# kossr2.net
KiCad netlist of a schematic drawn in EAGLE
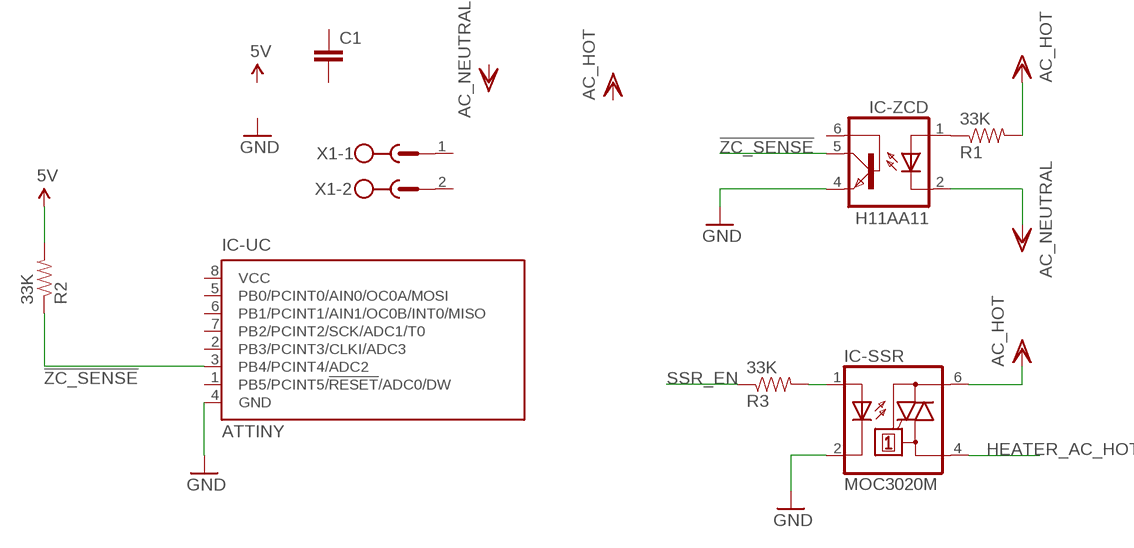
[diagram p0: schematic, sheet 1]

(export (version "E")
  (design (tool "Eeschema 10.0.6"))
  (components
    (comp (ref "C1")
      (value "CAPPTH")
      (footprint "eagle-import:CAP-PTH-SMALL")
      (libsource (lib "eagle-import") (part "CAPPTH"))
    )
    (comp (ref "IC-SSR")
      (value "MOC3020M")
      (footprint "eagle-import:DIL06")
      (fields (field (name "MF") "FAIRCHILD SEMICONDUCTOR") (field (name "MPN") "MOC3020-M"))
      (libsource (lib "eagle-import") (part "MOC30M20"))
    )
    (comp (ref "IC-UC")
      (value "ATTINY")
      (footprint "eagle-import:DIL08")
      (fields (field (name "MPN") "ATTINY13V-10PU"))
      (libsource (lib "eagle-import") (part "TINY13PUV-10"))
    )
    (comp (ref "IC-ZCD")
      (value "H11AA11")
      (footprint "eagle-import:DIL06")
      (fields (field (name "MPN") "H11A1-M"))
      (libsource (lib "eagle-import") (part "H11AA11"))
    )
    (comp (ref "R1")
      (value "33K")
      (footprint "eagle-import:AXIAL-0.4")
      (libsource (lib "eagle-import") (part "RESISTORPTH-1/4W"))
    )
    (comp (ref "R2")
      (value "33K")
      (footprint "eagle-import:AXIAL-0.4")
      (libsource (lib "eagle-import") (part "RESISTORPTH-1/4W"))
    )
    (comp (ref "R3")
      (value "33K")
      (footprint "eagle-import:AXIAL-0.4")
      (libsource (lib "eagle-import") (part "RESISTORPTH-1/4W"))
    )
    (comp (ref "X1")
      (value "MSTBV2")
      (footprint "eagle-import:MSTBV2")
      (libsource (lib "eagle-import") (part "MSTBV2"))
    )
  )
  (nets
    (net (code "1") (name "/HEATER_AC_HOT") (class "Default")
      (node (ref "IC-SSR") (pin "4") (pinfunction "A1_4") (pintype "passive"))
    )
    (net (code "2") (name "/SSR_EN") (class "Default")
      (node (ref "R3") (pin "P$1") (pinfunction "1_P$1") (pintype "passive"))
    )
    (net (code "3") (name "/VCC") (class "Default")
      (node (ref "IC-UC") (pin "8") (pinfunction "VCC_8") (pintype "power_in"))
    )
    (net (code "4") (name "/~{ZC_SENSE}") (class "Default")
      (node (ref "IC-UC") (pin "3") (pinfunction "PB4/PCINT4/ADC2_3") (pintype "bidirectional"))
      (node (ref "IC-ZCD") (pin "5") (pinfunction "COL_5") (pintype "passive"))
      (node (ref "R2") (pin "P$1") (pinfunction "1_P$1") (pintype "passive"))
    )
    (net (code "5") (name "5V") (class "Default")
      (node (ref "R2") (pin "P$2") (pinfunction "2_P$2") (pintype "passive"))
    )
    (net (code "6") (name "AC_HOT") (class "Default")
      (node (ref "IC-SSR") (pin "6") (pinfunction "A2_6") (pintype "passive"))
      (node (ref "R1") (pin "P$2") (pinfunction "2_P$2") (pintype "passive"))
    )
    (net (code "7") (name "AC_NEUTRAL") (class "Default")
      (node (ref "IC-ZCD") (pin "2") (pinfunction "C_2") (pintype "passive"))
    )
    (net (code "8") (name "GND") (class "Default")
      (node (ref "IC-SSR") (pin "2") (pinfunction "C_2") (pintype "passive"))
      (node (ref "IC-UC") (pin "4") (pinfunction "GND_4") (pintype "power_in"))
      (node (ref "IC-ZCD") (pin "4") (pinfunction "EMI_4") (pintype "passive"))
    )
    (net (code "9") (name "Net-(IC-SSR-A)") (class "Default")
      (node (ref "IC-SSR") (pin "1") (pinfunction "A_1") (pintype "passive"))
      (node (ref "R3") (pin "P$2") (pinfunction "2_P$2") (pintype "passive"))
    )
    (net (code "10") (name "Net-(IC-ZCD-A)") (class "Default")
      (node (ref "IC-ZCD") (pin "1") (pinfunction "A_1") (pintype "passive"))
      (node (ref "R1") (pin "P$1") (pinfunction "1_P$1") (pintype "passive"))
    )
    (net (code "11") (name "unconnected-(C1-Pad1)") (class "Default")
      (node (ref "C1") (pin "1") (pinfunction "1_1") (pintype "passive"))
    )
    (net (code "12") (name "unconnected-(C1-Pad2)") (class "Default")
      (node (ref "C1") (pin "2") (pinfunction "2_2") (pintype "passive"))
    )
    (net (code "13") (name "unconnected-(IC-UC-PB0{slash}PCINT0{slash}AIN0{slash}OC0A{slash}MOSI-Pad5)") (class "Default")
      (node (ref "IC-UC") (pin "5") (pinfunction "PB0/PCINT0/AIN0/OC0A/MOSI_5") (pintype "bidirectional"))
    )
    (net (code "14") (name "unconnected-(IC-UC-PB1{slash}PCINT1{slash}AIN1{slash}OC0B{slash}INT0{slash}MISO-Pad6)") (class "Default")
      (node (ref "IC-UC") (pin "6") (pinfunction "PB1/PCINT1/AIN1/OC0B/INT0/MISO_6") (pintype "bidirectional"))
    )
    (net (code "15") (name "unconnected-(IC-UC-PB2{slash}PCINT2{slash}SCK{slash}ADC1{slash}T0-Pad7)") (class "Default")
      (node (ref "IC-UC") (pin "7") (pinfunction "PB2/PCINT2/SCK/ADC1/T0_7") (pintype "bidirectional"))
    )
    (net (code "16") (name "unconnected-(IC-UC-PB3{slash}PCINT3{slash}CLKI{slash}ADC3-Pad2)") (class "Default")
      (node (ref "IC-UC") (pin "2") (pinfunction "PB3/PCINT3/CLKI/ADC3_2") (pintype "bidirectional"))
    )
    (net (code "17") (name "unconnected-(IC-UC-PB5{slash}PCINT5{slash}~{RESET}{slash}ADC0{slash}DW-Pad1)") (class "Default")
      (node (ref "IC-UC") (pin "1") (pinfunction "PB5/PCINT5/~{RESET}/ADC0/DW_1") (pintype "bidirectional"))
    )
    (net (code "18") (name "unconnected-(IC-ZCD-BAS-Pad6)") (class "Default")
      (node (ref "IC-ZCD") (pin "6") (pinfunction "BAS_6") (pintype "passive"))
    )
    (net (code "19") (name "unconnected-(X1A-SK-Pad1)") (class "Default")
      (node (ref "X1") (pin "1") (pinfunction "SK_1") (pintype "passive"))
    )
    (net (code "20") (name "unconnected-(X1B-SK-Pad2)") (class "Default")
      (node (ref "X1") (pin "2") (pinfunction "SK_2") (pintype "passive"))
    )
  )
)
